# Top_Overview.net
KiCad netlist of a schematic drawn in Altium Designer
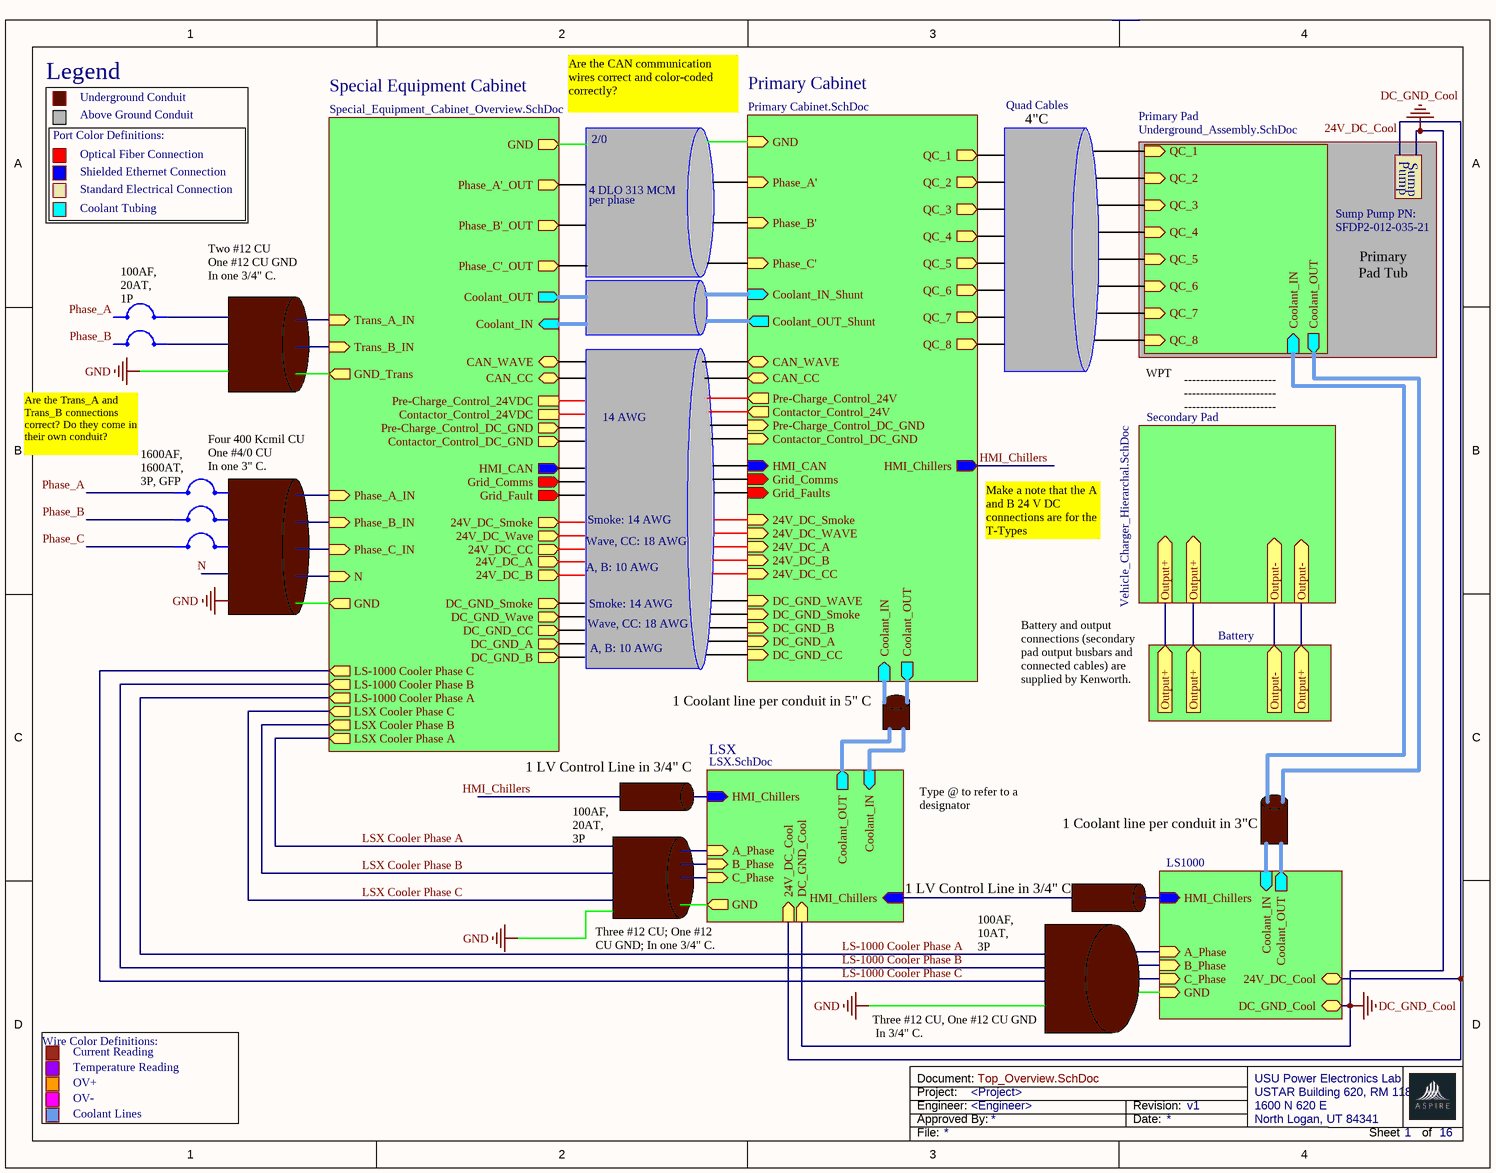
[diagram p0: Top_Overview.SchDoc]

(export (version "E")
  (design (tool "Eeschema 10.0.6"))
  (components
    (comp (ref "B1") (value "Breaker") (libsource (lib "Junctions") (part "Breaker")))
    (comp (ref "B2") (value "Breaker") (libsource (lib "Junctions") (part "Breaker")))
    (comp (ref "B3") (value "Breaker") (libsource (lib "Junctions") (part "Breaker")))
    (comp (ref "B6") (value "Breaker") (libsource (lib "Junctions") (part "Breaker")))
    (comp (ref "B7") (value "Breaker") (libsource (lib "Junctions") (part "Breaker")))
  )
  (nets
    (net (code "74") (name "/Phase_A") (class "Default")
      (node (ref "B1") (pin "0") (pinfunction "0_0") (pintype "passive"))
      (node (ref "B6") (pin "0") (pinfunction "0_0") (pintype "passive"))
    )
    (net (code "78") (name "/Phase_B") (class "Default")
      (node (ref "B2") (pin "0") (pinfunction "0_0") (pintype "passive"))
      (node (ref "B7") (pin "0") (pinfunction "0_0") (pintype "passive"))
    )
    (net (code "82") (name "/Phase_C") (class "Default")
      (node (ref "B3") (pin "0") (pinfunction "0_0") (pintype "passive"))
    )
    (net (code "110") (name "unconnected-(B1-Pad1)") (class "Default")
      (node (ref "B1") (pin "1") (pinfunction "1_1") (pintype "passive"))
    )
    (net (code "111") (name "unconnected-(B2-Pad1)") (class "Default")
      (node (ref "B2") (pin "1") (pinfunction "1_1") (pintype "passive"))
    )
    (net (code "112") (name "unconnected-(B3-Pad1)") (class "Default")
      (node (ref "B3") (pin "1") (pinfunction "1_1") (pintype "passive"))
    )
    (net (code "113") (name "unconnected-(B6-Pad1)") (class "Default")
      (node (ref "B6") (pin "1") (pinfunction "1_1") (pintype "passive"))
    )
    (net (code "114") (name "unconnected-(B7-Pad1)") (class "Default")
      (node (ref "B7") (pin "1") (pinfunction "1_1") (pintype "passive"))
    )
  )
)
